# ppg_array_wireless.net
KiCad netlist of a schematic drawn in EAGLE
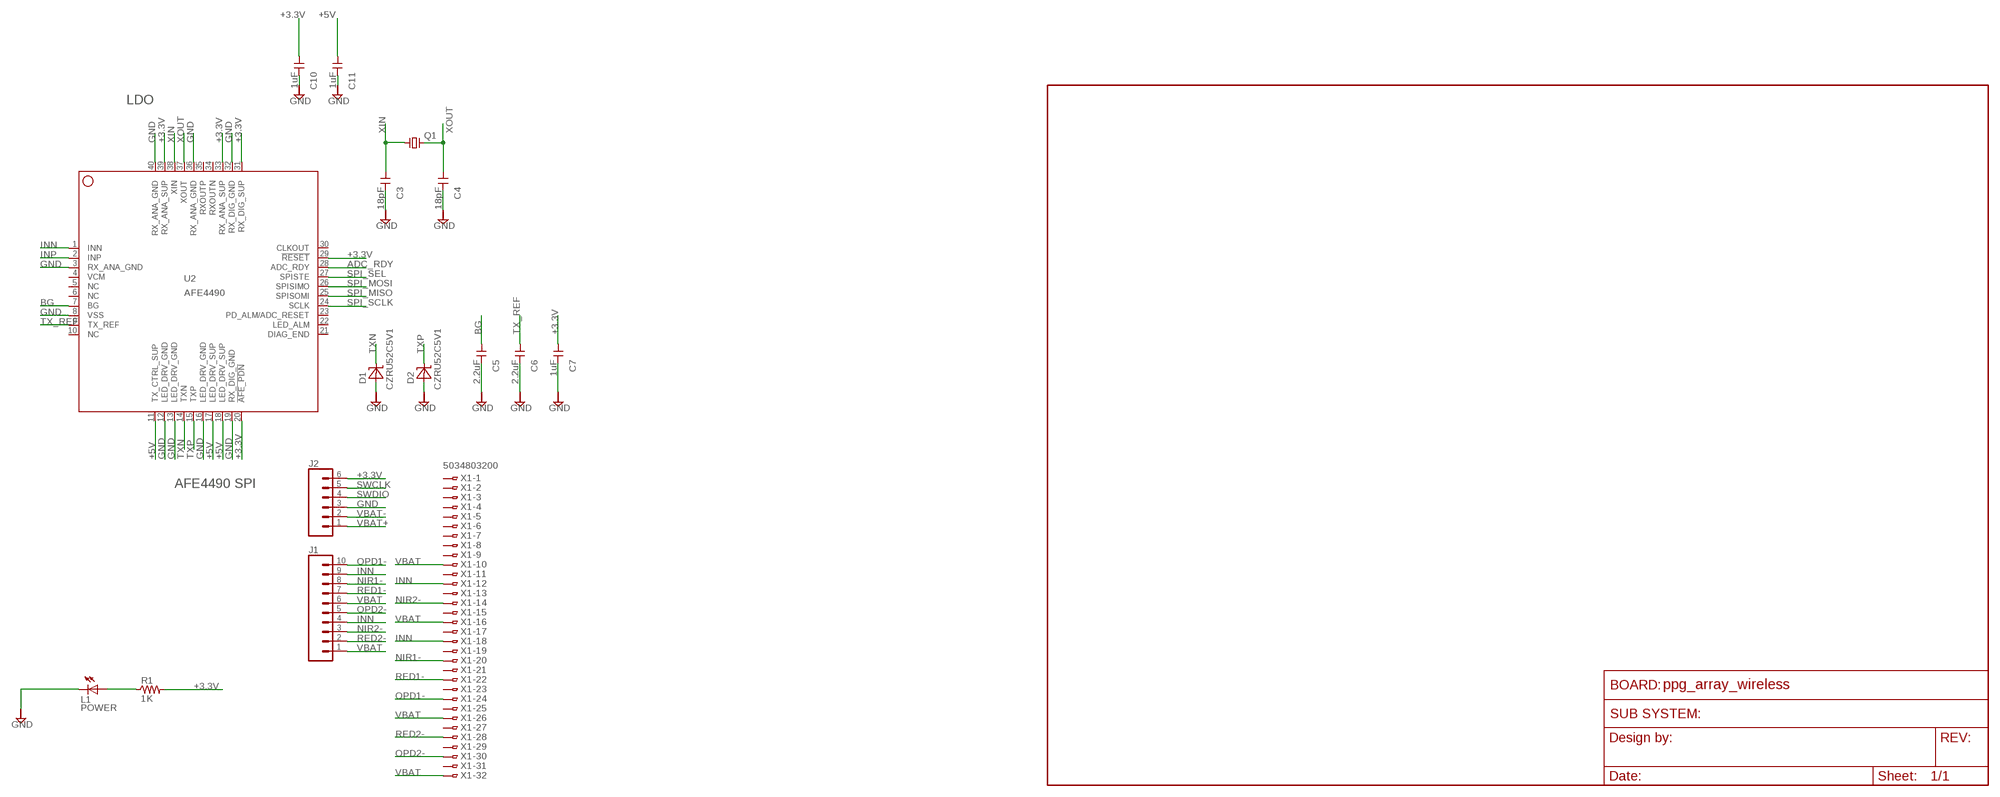
[diagram p0: schematic, sheet 1]

(export (version "E")
  (design (tool "Eeschema 10.0.6"))
  (components
    (comp (ref "C3")
      (value "18pF")
      (footprint "eagle-import:0603-CAP")
      (libsource (lib "eagle-import") (part "CAP0603-CAP"))
    )
    (comp (ref "C4")
      (value "18pF")
      (footprint "eagle-import:0603-CAP")
      (libsource (lib "eagle-import") (part "CAP0603-CAP"))
    )
    (comp (ref "C5")
      (value "2.2uF")
      (footprint "eagle-import:0603-CAP")
      (libsource (lib "eagle-import") (part "CAP0603-CAP"))
    )
    (comp (ref "C6")
      (value "2.2uF")
      (footprint "eagle-import:0603-CAP")
      (libsource (lib "eagle-import") (part "CAP0603-CAP"))
    )
    (comp (ref "C7")
      (value "1uF")
      (footprint "eagle-import:0603-CAP")
      (libsource (lib "eagle-import") (part "CAP0603-CAP"))
    )
    (comp (ref "C10")
      (value "1uF")
      (footprint "eagle-import:0603-CAP")
      (libsource (lib "eagle-import") (part "CAP0603-CAP"))
    )
    (comp (ref "C11")
      (value "1uF")
      (footprint "eagle-import:0603-CAP")
      (libsource (lib "eagle-import") (part "CAP0603-CAP"))
    )
    (comp (ref "D1")
      (value "CZRU52C5V1")
      (footprint "eagle-import:CZRU52C5V1")
      (libsource (lib "eagle-import") (part "CZRU52C5V1"))
    )
    (comp (ref "D2")
      (value "CZRU52C5V1")
      (footprint "eagle-import:CZRU52C5V1")
      (libsource (lib "eagle-import") (part "CZRU52C5V1"))
    )
    (comp (ref "J1")
      (value "CONN_10\"")
      (footprint "eagle-import:1X10")
      (libsource (lib "eagle-import") (part "CONN_10{dblquote}"))
    )
    (comp (ref "J2")
      (value "CONN_06SILK_FEMALE_PTH")
      (footprint "eagle-import:1X06")
      (libsource (lib "eagle-import") (part "CONN_06SILK_FEMALE_PTH"))
    )
    (comp (ref "L1")
      (value "POWER")
      (footprint "eagle-import:CHIP-LED0603")
      (libsource (lib "eagle-import") (part "LEDCHIP-LED0603"))
    )
    (comp (ref "Q1")
      (value "CRYSTAL_ECS_8MHZ")
      (footprint "eagle-import:XTAL_ECS-80-18-5PX-TR")
      (libsource (lib "eagle-import") (part "CRYSTAL_ECS_8MHZ"))
    )
    (comp (ref "R1")
      (value "1K")
      (footprint "eagle-import:R0603")
      (fields (field (name "MANUFACTURER") "Rohm Semiconductor"))
      (libsource (lib "eagle-import") (part "R-US_R0603"))
    )
    (comp (ref "U2")
      (value "AFE4490")
      (footprint "eagle-import:QFN40-6X6")
      (libsource (lib "eagle-import") (part "AFE4490"))
    )
    (comp (ref "X1")
      (value "5034803200")
      (footprint "eagle-import:5034803200")
      (libsource (lib "eagle-import") (part "5034803200"))
    )
  )
  (nets
    (net (code "1") (name "/+3.3V") (class "Default")
      (node (ref "C10") (pin "1") (pinfunction "1_1") (pintype "passive"))
      (node (ref "C7") (pin "1") (pinfunction "1_1") (pintype "passive"))
      (node (ref "J2") (pin "6") (pinfunction "6_6") (pintype "passive"))
      (node (ref "R1") (pin "2") (pinfunction "2_2") (pintype "passive"))
      (node (ref "U2") (pin "20") (pinfunction "~{AFE_PDN}_20") (pintype "input"))
      (node (ref "U2") (pin "29") (pinfunction "~{RESET}_29") (pintype "input"))
      (node (ref "U2") (pin "31") (pinfunction "RX_DIG_SUP_31") (pintype "power_in"))
      (node (ref "U2") (pin "33") (pinfunction "RX_ANA_SUP_33") (pintype "power_in"))
      (node (ref "U2") (pin "39") (pinfunction "RX_ANA_SUP_39") (pintype "power_in"))
    )
    (net (code "2") (name "/+5V") (class "Default")
      (node (ref "C11") (pin "1") (pinfunction "1_1") (pintype "passive"))
      (node (ref "U2") (pin "11") (pinfunction "TX_CTRL_SUP_11") (pintype "power_in"))
      (node (ref "U2") (pin "17") (pinfunction "LED_DRV_SUP_17") (pintype "power_in"))
      (node (ref "U2") (pin "18") (pinfunction "LED_DRV_SUP_18") (pintype "power_in"))
    )
    (net (code "3") (name "/ADC_RDY") (class "Default")
      (node (ref "U2") (pin "28") (pinfunction "ADC_RDY_28") (pintype "output"))
    )
    (net (code "4") (name "/BG") (class "Default")
      (node (ref "C5") (pin "1") (pinfunction "1_1") (pintype "passive"))
      (node (ref "U2") (pin "7") (pinfunction "BG_7") (pintype "passive"))
    )
    (net (code "5") (name "/INN") (class "Default")
      (node (ref "J1") (pin "4") (pinfunction "4_4") (pintype "passive"))
      (node (ref "J1") (pin "9") (pinfunction "9_9") (pintype "passive"))
      (node (ref "U2") (pin "1") (pinfunction "INN_1") (pintype "input"))
      (node (ref "X1") (pin "12") (pinfunction "1_12") (pintype "passive"))
      (node (ref "X1") (pin "18") (pinfunction "1_18") (pintype "passive"))
    )
    (net (code "6") (name "/INP") (class "Default")
      (node (ref "U2") (pin "2") (pinfunction "INP_2") (pintype "input"))
    )
    (net (code "7") (name "/NIR1-") (class "Default")
      (node (ref "J1") (pin "8") (pinfunction "8_8") (pintype "passive"))
      (node (ref "X1") (pin "20") (pinfunction "1_20") (pintype "passive"))
    )
    (net (code "8") (name "/NIR2-") (class "Default")
      (node (ref "J1") (pin "3") (pinfunction "3_3") (pintype "passive"))
      (node (ref "X1") (pin "14") (pinfunction "1_14") (pintype "passive"))
    )
    (net (code "9") (name "/OPD1-") (class "Default")
      (node (ref "J1") (pin "10") (pinfunction "10_10") (pintype "passive"))
      (node (ref "X1") (pin "24") (pinfunction "1_24") (pintype "passive"))
    )
    (net (code "10") (name "/OPD2-") (class "Default")
      (node (ref "J1") (pin "5") (pinfunction "5_5") (pintype "passive"))
      (node (ref "X1") (pin "30") (pinfunction "1_30") (pintype "passive"))
    )
    (net (code "11") (name "/RED1-") (class "Default")
      (node (ref "J1") (pin "7") (pinfunction "7_7") (pintype "passive"))
      (node (ref "X1") (pin "22") (pinfunction "1_22") (pintype "passive"))
    )
    (net (code "12") (name "/RED2-") (class "Default")
      (node (ref "J1") (pin "2") (pinfunction "2_2") (pintype "passive"))
      (node (ref "X1") (pin "28") (pinfunction "1_28") (pintype "passive"))
    )
    (net (code "13") (name "/SPI_MISO") (class "Default")
      (node (ref "U2") (pin "25") (pinfunction "SPISOMI_25") (pintype "output"))
    )
    (net (code "14") (name "/SPI_MOSI") (class "Default")
      (node (ref "U2") (pin "26") (pinfunction "SPISIMO_26") (pintype "input"))
    )
    (net (code "15") (name "/SPI_SCLK") (class "Default")
      (node (ref "U2") (pin "24") (pinfunction "SCLK_24") (pintype "input"))
    )
    (net (code "16") (name "/SPI_SEL") (class "Default")
      (node (ref "U2") (pin "27") (pinfunction "SPISTE_27") (pintype "input"))
    )
    (net (code "17") (name "/SWCLK") (class "Default")
      (node (ref "J2") (pin "5") (pinfunction "5_5") (pintype "passive"))
    )
    (net (code "18") (name "/SWDIO") (class "Default")
      (node (ref "J2") (pin "4") (pinfunction "4_4") (pintype "passive"))
    )
    (net (code "19") (name "/TXN") (class "Default")
      (node (ref "D1") (pin "C") (pinfunction "C_C") (pintype "passive"))
      (node (ref "U2") (pin "14") (pinfunction "TXN_14") (pintype "output"))
    )
    (net (code "20") (name "/TXP") (class "Default")
      (node (ref "D2") (pin "C") (pinfunction "C_C") (pintype "passive"))
      (node (ref "U2") (pin "15") (pinfunction "TXP_15") (pintype "output"))
    )
    (net (code "21") (name "/TX_REF") (class "Default")
      (node (ref "C6") (pin "1") (pinfunction "1_1") (pintype "passive"))
      (node (ref "U2") (pin "9") (pinfunction "TX_REF_9") (pintype "output"))
    )
    (net (code "22") (name "/VBAT") (class "Default")
      (node (ref "J1") (pin "1") (pinfunction "1_1") (pintype "passive"))
      (node (ref "J1") (pin "6") (pinfunction "6_6") (pintype "passive"))
      (node (ref "X1") (pin "10") (pinfunction "1_10") (pintype "passive"))
      (node (ref "X1") (pin "16") (pinfunction "1_16") (pintype "passive"))
      (node (ref "X1") (pin "26") (pinfunction "1_26") (pintype "passive"))
      (node (ref "X1") (pin "32") (pinfunction "1_32") (pintype "passive"))
    )
    (net (code "23") (name "/VBAT+") (class "Default")
      (node (ref "J2") (pin "1") (pinfunction "1_1") (pintype "passive"))
    )
    (net (code "24") (name "/VBAT-") (class "Default")
      (node (ref "J2") (pin "2") (pinfunction "2_2") (pintype "passive"))
    )
    (net (code "25") (name "/XIN") (class "Default")
      (node (ref "C3") (pin "1") (pinfunction "1_1") (pintype "passive"))
      (node (ref "Q1") (pin "1") (pinfunction "A_1") (pintype "passive"))
      (node (ref "U2") (pin "38") (pinfunction "XIN_38") (pintype "input"))
    )
    (net (code "26") (name "/XOUT") (class "Default")
      (node (ref "C4") (pin "1") (pinfunction "1_1") (pintype "passive"))
      (node (ref "Q1") (pin "2") (pinfunction "B_2") (pintype "passive"))
      (node (ref "U2") (pin "37") (pinfunction "XOUT_37") (pintype "output"))
    )
    (net (code "27") (name "GND") (class "Default")
      (node (ref "C10") (pin "2") (pinfunction "2_2") (pintype "passive"))
      (node (ref "C11") (pin "2") (pinfunction "2_2") (pintype "passive"))
      (node (ref "C3") (pin "2") (pinfunction "2_2") (pintype "passive"))
      (node (ref "C4") (pin "2") (pinfunction "2_2") (pintype "passive"))
      (node (ref "C5") (pin "2") (pinfunction "2_2") (pintype "passive"))
      (node (ref "C6") (pin "2") (pinfunction "2_2") (pintype "passive"))
      (node (ref "C7") (pin "2") (pinfunction "2_2") (pintype "passive"))
      (node (ref "D1") (pin "A") (pinfunction "A_A") (pintype "passive"))
      (node (ref "D2") (pin "A") (pinfunction "A_A") (pintype "passive"))
      (node (ref "J2") (pin "3") (pinfunction "3_3") (pintype "passive"))
      (node (ref "L1") (pin "C") (pinfunction "C_C") (pintype "passive"))
      (node (ref "U2") (pin "12") (pinfunction "LED_DRV_GND_12") (pintype "power_in"))
      (node (ref "U2") (pin "13") (pinfunction "LED_DRV_GND_13") (pintype "power_in"))
      (node (ref "U2") (pin "16") (pinfunction "LED_DRV_GND_16") (pintype "power_in"))
      (node (ref "U2") (pin "19") (pinfunction "RX_DIG_GND_19") (pintype "power_in"))
      (node (ref "U2") (pin "3") (pinfunction "RX_ANA_GND_3") (pintype "power_in"))
      (node (ref "U2") (pin "32") (pinfunction "RX_DIG_GND_32") (pintype "power_in"))
      (node (ref "U2") (pin "36") (pinfunction "RX_ANA_GND_36") (pintype "power_in"))
      (node (ref "U2") (pin "40") (pinfunction "RX_ANA_GND_40") (pintype "power_in"))
      (node (ref "U2") (pin "8") (pinfunction "VSS_8") (pintype "power_in"))
    )
    (net (code "28") (name "Net-(L1-PadA)") (class "Default")
      (node (ref "L1") (pin "A") (pinfunction "A_A") (pintype "passive"))
      (node (ref "R1") (pin "1") (pinfunction "1_1") (pintype "passive"))
    )
    (net (code "29") (name "unconnected-(U2A-CLKOUT-Pad30)") (class "Default")
      (node (ref "U2") (pin "30") (pinfunction "CLKOUT_30") (pintype "output"))
    )
    (net (code "30") (name "unconnected-(U2A-DIAG_END-Pad21)") (class "Default")
      (node (ref "U2") (pin "21") (pinfunction "DIAG_END_21") (pintype "output"))
    )
    (net (code "31") (name "unconnected-(U2A-LED_ALM-Pad22)") (class "Default")
      (node (ref "U2") (pin "22") (pinfunction "LED_ALM_22") (pintype "output"))
    )
    (net (code "32") (name "unconnected-(U2A-NC-Pad5)") (class "Default")
      (node (ref "U2") (pin "5") (pinfunction "NC_5") (pintype "no_connect"))
    )
    (net (code "33") (name "unconnected-(U2A-NC-Pad6)") (class "Default")
      (node (ref "U2") (pin "6") (pinfunction "NC_6") (pintype "no_connect"))
    )
    (net (code "34") (name "unconnected-(U2A-NC-Pad10)") (class "Default")
      (node (ref "U2") (pin "10") (pinfunction "NC_10") (pintype "no_connect"))
    )
    (net (code "35") (name "unconnected-(U2A-PD_ALM{slash}ADC_RESET-Pad23)") (class "Default")
      (node (ref "U2") (pin "23") (pinfunction "PD_ALM/ADC_RESET_23") (pintype "bidirectional"))
    )
    (net (code "36") (name "unconnected-(U2A-RXOUTN-Pad34)") (class "Default")
      (node (ref "U2") (pin "34") (pinfunction "RXOUTN_34") (pintype "output"))
    )
    (net (code "37") (name "unconnected-(U2A-RXOUTP-Pad35)") (class "Default")
      (node (ref "U2") (pin "35") (pinfunction "RXOUTP_35") (pintype "output"))
    )
    (net (code "38") (name "unconnected-(U2A-VCM-Pad4)") (class "Default")
      (node (ref "U2") (pin "4") (pinfunction "VCM_4") (pintype "output"))
    )
    (net (code "39") (name "unconnected-(X1-Pad1)") (class "Default")
      (node (ref "X1") (pin "1") (pinfunction "1_1") (pintype "passive"))
    )
    (net (code "40") (name "unconnected-(X1AA-1-Pad4)") (class "Default")
      (node (ref "X1") (pin "4") (pinfunction "1_4") (pintype "passive"))
    )
    (net (code "41") (name "unconnected-(X1AB-1-Pad5)") (class "Default")
      (node (ref "X1") (pin "5") (pinfunction "1_5") (pintype "passive"))
    )
    (net (code "42") (name "unconnected-(X1AC-1-Pad6)") (class "Default")
      (node (ref "X1") (pin "6") (pinfunction "1_6") (pintype "passive"))
    )
    (net (code "43") (name "unconnected-(X1AD-1-Pad7)") (class "Default")
      (node (ref "X1") (pin "7") (pinfunction "1_7") (pintype "passive"))
    )
    (net (code "44") (name "unconnected-(X1AE-1-Pad8)") (class "Default")
      (node (ref "X1") (pin "8") (pinfunction "1_8") (pintype "passive"))
    )
    (net (code "45") (name "unconnected-(X1AF-1-Pad9)") (class "Default")
      (node (ref "X1") (pin "9") (pinfunction "1_9") (pintype "passive"))
    )
    (net (code "46") (name "unconnected-(X1C-1-Pad11)") (class "Default")
      (node (ref "X1") (pin "11") (pinfunction "1_11") (pintype "passive"))
    )
    (net (code "47") (name "unconnected-(X1E-1-Pad13)") (class "Default")
      (node (ref "X1") (pin "13") (pinfunction "1_13") (pintype "passive"))
    )
    (net (code "48") (name "unconnected-(X1G-1-Pad15)") (class "Default")
      (node (ref "X1") (pin "15") (pinfunction "1_15") (pintype "passive"))
    )
    (net (code "49") (name "unconnected-(X1I-1-Pad17)") (class "Default")
      (node (ref "X1") (pin "17") (pinfunction "1_17") (pintype "passive"))
    )
    (net (code "50") (name "unconnected-(X1K-1-Pad19)") (class "Default")
      (node (ref "X1") (pin "19") (pinfunction "1_19") (pintype "passive"))
    )
    (net (code "51") (name "unconnected-(X1L-1-Pad2)") (class "Default")
      (node (ref "X1") (pin "2") (pinfunction "1_2") (pintype "passive"))
    )
    (net (code "52") (name "unconnected-(X1N-1-Pad21)") (class "Default")
      (node (ref "X1") (pin "21") (pinfunction "1_21") (pintype "passive"))
    )
    (net (code "53") (name "unconnected-(X1P-1-Pad23)") (class "Default")
      (node (ref "X1") (pin "23") (pinfunction "1_23") (pintype "passive"))
    )
    (net (code "54") (name "unconnected-(X1R-1-Pad25)") (class "Default")
      (node (ref "X1") (pin "25") (pinfunction "1_25") (pintype "passive"))
    )
    (net (code "55") (name "unconnected-(X1T-1-Pad27)") (class "Default")
      (node (ref "X1") (pin "27") (pinfunction "1_27") (pintype "passive"))
    )
    (net (code "56") (name "unconnected-(X1V-1-Pad29)") (class "Default")
      (node (ref "X1") (pin "29") (pinfunction "1_29") (pintype "passive"))
    )
    (net (code "57") (name "unconnected-(X1W-1-Pad3)") (class "Default")
      (node (ref "X1") (pin "3") (pinfunction "1_3") (pintype "passive"))
    )
    (net (code "58") (name "unconnected-(X1Y-1-Pad31)") (class "Default")
      (node (ref "X1") (pin "31") (pinfunction "1_31") (pintype "passive"))
    )
  )
)
